# Microphone-Boards_V1_0_GMA3526H10.net
KiCad netlist of a schematic drawn in Altium Designer
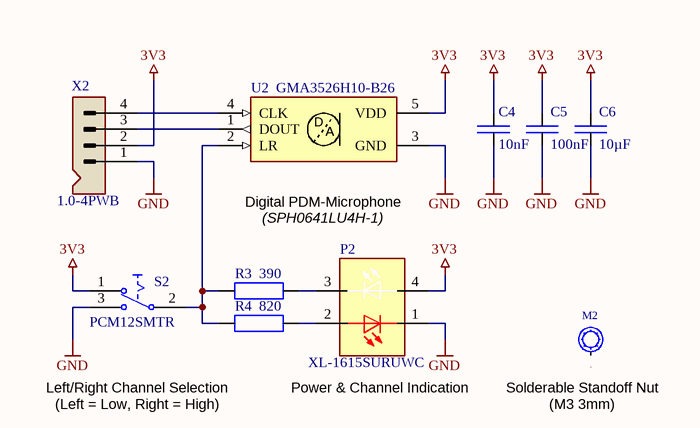
[diagram p0: Microphone-Boards_V1.0_GMA3526H10.SchDoc]

(export (version "E")
  (design (tool "Eeschema 10.0.6"))
  (components
    (comp (ref "C4")
      (value "10nF")
      (footprint "SMD Keramikkondensator 0603")
      (description "CAP-MK")
      (libsource (lib "AudioAmp") (part "C-CAPACITOR"))
    )
    (comp (ref "C5")
      (value "100nF")
      (footprint "SMD Keramikkondensator 0603")
      (description "SMD Ceramic Capacitor E6")
      (libsource (lib "Ceramic Capacitors-E6") (part "E6 - 100nF"))
    )
    (comp (ref "C6")
      (value "10µF")
      (footprint "SMD Keramikkondensator 1206")
      (description "SMD Ceramic Capacitor E6")
      (libsource (lib "Ceramic Capacitors-E6") (part "E6 - 10uF"))
    )
    (comp (ref "M2")
      (value "SMTSO-M3-3ET")
      (footprint "SMD Solder-Nut (M3 3mm)")
      (description "Solderable Standoff Nut")
      (libsource (lib "Velotour_2022") (part "M-Spacer_M3_3mm"))
    )
    (comp (ref "P2")
      (value "XL-1615SURUWC")
      (footprint "SMD LED 0606")
      (description "LED Red/White")
      (libsource (lib "Microphone-Boards") (part "P-XL-1615SURUWC"))
    )
    (comp (ref "R3")
      (value "390")
      (footprint "SMD Widerstand 0603")
      (description "SMD-Widerstand 1/4W")
      (libsource (lib "Backplane_1") (part "R-RESISTOR"))
    )
    (comp (ref "R4")
      (value "820")
      (footprint "SMD Widerstand 0603")
      (description "SMD-Widerstand 1/4W")
      (libsource (lib "Backplane_1") (part "R-RESISTOR"))
    )
    (comp (ref "S2")
      (value "PCM12SMTR")
      (footprint "SMD Switch SPDT (PCM12SMTR)")
      (description "Miniature Slide Switch")
      (libsource (lib "Custom ST-Link") (part "S-PCM12SMTR"))
    )
    (comp (ref "U2")
      (value "GMA3526H10-B26")
      (footprint "SMD Microphone (GMA3526H10-B26)")
      (description "Digital PDM MEMS Microphone (Bottom Port)")
      (libsource (lib "Microphone-Boards") (part "U-GMA3526H10-B26"))
    )
    (comp (ref "X2")
      (value "1.0-4PWB")
      (footprint "SMD Connector (SM04B-SRSS-TB)")
      (description "Wire To Board Connector (1x4P 1.0mm)")
      (libsource (lib "Audio-Beamformer") (part "X-Stiftleiste (4-Fach)"))
    )
  )
  (nets
    (net (code "1") (name "/M") (class "Default")
      (node (ref "M2") (pin "1") (pinfunction "1_1") (pintype "passive"))
    )
    (net (code "2") (name "3V3") (class "Default")
      (node (ref "C4") (pin "2") (pinfunction "2_2") (pintype "passive"))
      (node (ref "C5") (pin "2") (pinfunction "2_2") (pintype "passive"))
      (node (ref "C6") (pin "2") (pinfunction "2_2") (pintype "passive"))
      (node (ref "P2") (pin "4") (pinfunction "WA_4") (pintype "passive"))
      (node (ref "S2") (pin "1") (pinfunction "NC1_1") (pintype "passive"))
      (node (ref "U2") (pin "5") (pinfunction "VDD_5") (pintype "power_in"))
      (node (ref "X2") (pin "2") (pinfunction "2_2") (pintype "passive"))
    )
    (net (code "3") (name "GND") (class "Default")
      (node (ref "C4") (pin "1") (pinfunction "1_1") (pintype "passive"))
      (node (ref "C5") (pin "1") (pinfunction "1_1") (pintype "passive"))
      (node (ref "C6") (pin "1") (pinfunction "1_1") (pintype "passive"))
      (node (ref "P2") (pin "1") (pinfunction "RC_1") (pintype "passive"))
      (node (ref "S2") (pin "3") (pinfunction "NO1_3") (pintype "passive"))
      (node (ref "U2") (pin "3") (pinfunction "GND_3") (pintype "power_in"))
      (node (ref "X2") (pin "1") (pinfunction "1_1") (pintype "passive"))
    )
    (net (code "4") (name "Net-(P2-RA)") (class "Default")
      (node (ref "P2") (pin "2") (pinfunction "RA_2") (pintype "passive"))
      (node (ref "R4") (pin "2") (pinfunction "2_2") (pintype "passive"))
    )
    (net (code "5") (name "Net-(P2-WC)") (class "Default")
      (node (ref "P2") (pin "3") (pinfunction "WC_3") (pintype "passive"))
      (node (ref "R3") (pin "2") (pinfunction "2_2") (pintype "passive"))
    )
    (net (code "6") (name "Net-(S2-COMMON1)") (class "Default")
      (node (ref "R3") (pin "1") (pinfunction "1_1") (pintype "passive"))
      (node (ref "R4") (pin "1") (pinfunction "1_1") (pintype "passive"))
      (node (ref "S2") (pin "2") (pinfunction "COMMON1_2") (pintype "passive"))
      (node (ref "U2") (pin "2") (pinfunction "LR_2") (pintype "input"))
    )
    (net (code "7") (name "Net-(U2-CLK)") (class "Default")
      (node (ref "U2") (pin "4") (pinfunction "CLK_4") (pintype "input"))
      (node (ref "X2") (pin "4") (pinfunction "4_4") (pintype "passive"))
    )
    (net (code "8") (name "Net-(U2-DOUT)") (class "Default")
      (node (ref "U2") (pin "1") (pinfunction "DOUT_1") (pintype "output"))
      (node (ref "X2") (pin "3") (pinfunction "3_3") (pintype "passive"))
    )
  )
)
